# MD017A_ISO-F28027F_0.net
KiCad netlist of a schematic drawn in Altium Designer
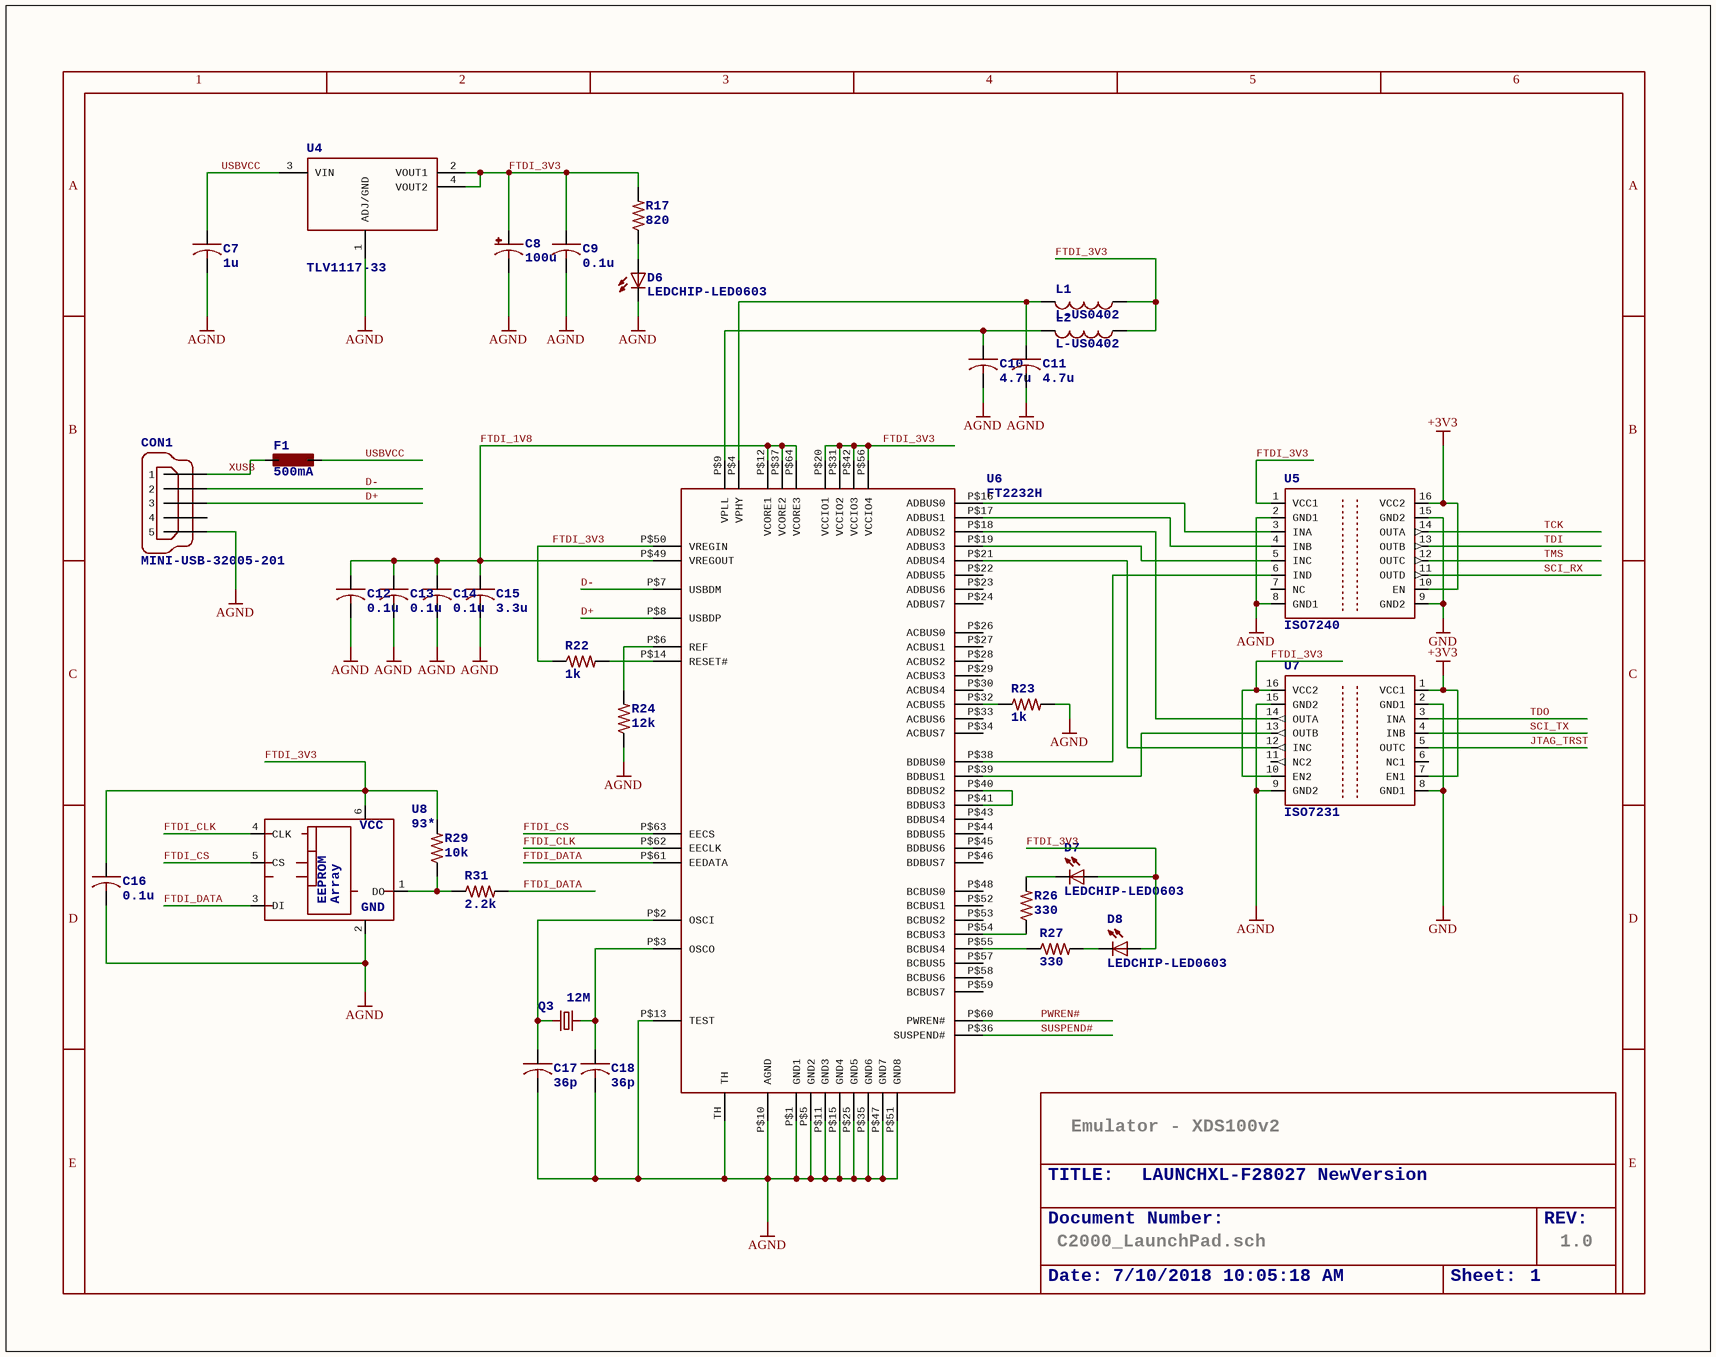
[diagram p0: MD017A ISO-F28027F_0.SchDoc]

(export (version "E")
  (design (tool "Eeschema 10.0.6"))
  (components
    (comp (ref "C7")
      (value "1u")
      (footprint "C0402")
      (description "CAPACITOR, American symbol")
      (libsource (lib "rcl") (part "C-USC0402"))
    )
    (comp (ref "C8")
      (value "100u")
      (footprint "B/3528-21R")
      (description "POLARIZED CAPACITOR, American symbol")
      (libsource (lib "rcl") (part "CPOL-USB/3528-21R"))
    )
    (comp (ref "C9")
      (value "0.1u")
      (footprint "C0402")
      (description "CAPACITOR, American symbol")
      (libsource (lib "rcl") (part "C-USC0402"))
    )
    (comp (ref "C10")
      (value "4.7u")
      (footprint "C0402")
      (description "CAPACITOR, American symbol")
      (libsource (lib "rcl") (part "C-USC0402"))
    )
    (comp (ref "C11")
      (value "4.7u")
      (footprint "C0402")
      (description "CAPACITOR, American symbol")
      (libsource (lib "rcl") (part "C-USC0402"))
    )
    (comp (ref "C12")
      (value "0.1u")
      (footprint "C0402")
      (description "CAPACITOR, American symbol")
      (libsource (lib "rcl") (part "C-USC0402"))
    )
    (comp (ref "C13")
      (value "0.1u")
      (footprint "C0402")
      (description "CAPACITOR, American symbol")
      (libsource (lib "rcl") (part "C-USC0402"))
    )
    (comp (ref "C14")
      (value "0.1u")
      (footprint "C0402")
      (description "CAPACITOR, American symbol")
      (libsource (lib "rcl") (part "C-USC0402"))
    )
    (comp (ref "C15")
      (value "3.3u")
      (footprint "C0402")
      (description "CAPACITOR, American symbol")
      (libsource (lib "rcl") (part "C-USC0402"))
    )
    (comp (ref "C16")
      (value "0.1u")
      (footprint "C0402")
      (description "CAPACITOR, American symbol")
      (libsource (lib "rcl") (part "C-USC0402"))
    )
    (comp (ref "C17")
      (value "36p")
      (footprint "C0402")
      (description "CAPACITOR, American symbol")
      (libsource (lib "rcl") (part "C-USC0402"))
    )
    (comp (ref "C18")
      (value "36p")
      (footprint "C0402")
      (description "CAPACITOR, American symbol")
      (libsource (lib "rcl") (part "C-USC0402"))
    )
    (comp (ref "CON1")
      (value "MINI-USB-32005-201")
      (footprint "32005-201")
      (description "MINI USB-B Conector   Source: www.cypressindustries.com")
      (libsource (lib "con-cypressindustries") (part "MINI-USB-32005-201"))
    )
    (comp (ref "D6")
      (value "LEDCHIP-LED0603")
      (footprint "CHIP-LED0603")
      (libsource (lib "led") (part "LEDCHIP-LED0603"))
    )
    (comp (ref "D7")
      (value "LEDCHIP-LED0603")
      (footprint "CHIP-LED0603")
      (libsource (lib "led") (part "LEDCHIP-LED0603"))
    )
    (comp (ref "D8")
      (value "LEDCHIP-LED0603")
      (footprint "CHIP-LED0603")
      (libsource (lib "led") (part "LEDCHIP-LED0603"))
    )
    (comp (ref "F1")
      (value "500mA")
      (footprint "L1812")
      (description "INDUCTOR, European symbol")
      (libsource (lib "rcl") (part "L-EUL1812"))
    )
    (comp (ref "L1")
      (value "L-US0402")
      (footprint "R0402")
      (description "INDUCTOR, American symbol")
      (libsource (lib "rcl") (part "L-US0402"))
    )
    (comp (ref "L2")
      (value "L-US0402")
      (footprint "R0402")
      (description "INDUCTOR, American symbol")
      (libsource (lib "rcl") (part "L-US0402"))
    )
    (comp (ref "Q3")
      (value "12M")
      (footprint "HC49UP")
      (description "CRYSTAL")
      (libsource (lib "crystal") (part "CRYSTALHC49UP"))
    )
    (comp (ref "R17")
      (value "820")
      (footprint "R0402")
      (description "RESISTOR, American symbol")
      (libsource (lib "rcl") (part "R-US_R0402"))
    )
    (comp (ref "R22")
      (value "1k")
      (footprint "R0402")
      (description "RESISTOR, American symbol")
      (libsource (lib "rcl") (part "R-US_R0402"))
    )
    (comp (ref "R23")
      (value "1k")
      (footprint "R0402")
      (description "RESISTOR, American symbol")
      (libsource (lib "rcl") (part "R-US_R0402"))
    )
    (comp (ref "R24")
      (value "12k")
      (footprint "R0402")
      (description "RESISTOR, American symbol")
      (libsource (lib "rcl") (part "R-US_R0402"))
    )
    (comp (ref "R26")
      (value "330")
      (footprint "R0402")
      (description "RESISTOR, American symbol")
      (libsource (lib "rcl") (part "R-US_R0402"))
    )
    (comp (ref "R27")
      (value "330")
      (footprint "R0402")
      (description "RESISTOR, American symbol")
      (libsource (lib "rcl") (part "R-US_R0402"))
    )
    (comp (ref "R29")
      (value "10k")
      (footprint "R0402")
      (description "RESISTOR, American symbol")
      (libsource (lib "rcl") (part "R-US_R0402"))
    )
    (comp (ref "R31")
      (value "2.2k")
      (footprint "R0402")
      (description "RESISTOR, American symbol")
      (libsource (lib "rcl") (part "R-US_R0402"))
    )
    (comp (ref "U4") (value "TLV1117-33") (footprint "SOT223") (libsource (lib "texas") (part "TLV1117-33")))
    (comp (ref "U5")
      (value "ISO7240")
      (footprint "SO-16DW")
      (description "HIGH SPEED QUAD DIGITAL ISOLATORS   Source: http://focus.ti.com/lit/ds/symlink/iso7240m.pdf")
      (fields (field (name "MPN") "ISO7240MDW"))
      (libsource (lib "texas") (part "ISO7240"))
    )
    (comp (ref "U6") (value "FT2232H") (footprint "QFN64") (libsource (lib "ti_trey") (part "FT2232H")))
    (comp (ref "U7") (value "ISO7231") (footprint "SO-16DW") (libsource (lib "texas") (part "ISO7231")))
    (comp (ref "U8")
      (value "93*")
      (footprint "SOT23-6")
      (description "Serial EPROM   1 K/2 K/4 K, low voltage, Microwire")
      (fields
        (field (name "ARRAY") "Array")
        (field (name "VCC") "VCC")
        (field (name "GND") "GND")
        (field (name "EEPROM") "EEPROM")
      )
      (libsource (lib "ti_trey") (part "93*"))
    )
  )
  (nets
    (net (code "1") (name "+3V3") (class "Default")
      (node (ref "U5") (pin "10") (pinfunction "EN_10") (pintype "passive"))
      (node (ref "U5") (pin "16") (pinfunction "VCC2_16") (pintype "power_in"))
      (node (ref "U7") (pin "1") (pinfunction "VCC1_1") (pintype "power_in"))
      (node (ref "U7") (pin "7") (pinfunction "EN1_7") (pintype "passive"))
    )
    (net (code "2") (name "/D+") (class "Default")
      (node (ref "CON1") (pin "3") (pinfunction "3_3") (pintype "passive"))
      (node (ref "U6") (pin "P$8") (pinfunction "USBDP_P$8") (pintype "passive"))
    )
    (net (code "3") (name "/D-") (class "Default")
      (node (ref "CON1") (pin "2") (pinfunction "2_2") (pintype "passive"))
      (node (ref "U6") (pin "P$7") (pinfunction "USBDM_P$7") (pintype "passive"))
    )
    (net (code "4") (name "/FTDI_1V8") (class "Default")
      (node (ref "C12") (pin "1") (pinfunction "1_1") (pintype "passive"))
      (node (ref "C13") (pin "1") (pinfunction "1_1") (pintype "passive"))
      (node (ref "C14") (pin "1") (pinfunction "1_1") (pintype "passive"))
      (node (ref "C15") (pin "1") (pinfunction "1_1") (pintype "passive"))
      (node (ref "U6") (pin "P$12") (pinfunction "VCORE1_P$12") (pintype "passive"))
      (node (ref "U6") (pin "P$37") (pinfunction "VCORE2_P$37") (pintype "passive"))
      (node (ref "U6") (pin "P$49") (pinfunction "VREGOUT_P$49") (pintype "passive"))
      (node (ref "U6") (pin "P$64") (pinfunction "VCORE3_P$64") (pintype "passive"))
    )
    (net (code "5") (name "/FTDI_3V3") (class "Default")
      (node (ref "C16") (pin "1") (pinfunction "1_1") (pintype "passive"))
      (node (ref "C8") (pin "+") (pinfunction "+_+") (pintype "passive"))
      (node (ref "C9") (pin "1") (pinfunction "1_1") (pintype "passive"))
      (node (ref "D7") (pin "A") (pinfunction "A_A") (pintype "passive"))
      (node (ref "D8") (pin "A") (pinfunction "A_A") (pintype "passive"))
      (node (ref "L1") (pin "1") (pinfunction "1_1") (pintype "passive"))
      (node (ref "L2") (pin "1") (pinfunction "1_1") (pintype "passive"))
      (node (ref "R17") (pin "2") (pinfunction "2_2") (pintype "passive"))
      (node (ref "R22") (pin "1") (pinfunction "1_1") (pintype "passive"))
      (node (ref "R29") (pin "2") (pinfunction "2_2") (pintype "passive"))
      (node (ref "U4") (pin "2") (pinfunction "VOUT1_2") (pintype "passive"))
      (node (ref "U4") (pin "4") (pinfunction "VOUT2_4") (pintype "passive"))
      (node (ref "U5") (pin "1") (pinfunction "VCC1_1") (pintype "power_in"))
      (node (ref "U6") (pin "P$20") (pinfunction "VCCIO1_P$20") (pintype "passive"))
      (node (ref "U6") (pin "P$31") (pinfunction "VCCIO2_P$31") (pintype "passive"))
      (node (ref "U6") (pin "P$42") (pinfunction "VCCIO3_P$42") (pintype "passive"))
      (node (ref "U6") (pin "P$50") (pinfunction "VREGIN_P$50") (pintype "passive"))
      (node (ref "U6") (pin "P$56") (pinfunction "VCCIO4_P$56") (pintype "passive"))
      (node (ref "U7") (pin "10") (pinfunction "EN2_10") (pintype "passive"))
      (node (ref "U7") (pin "16") (pinfunction "VCC2_16") (pintype "power_in"))
      (node (ref "U8") (pin "6") (pinfunction "VCC_6") (pintype "power_in"))
    )
    (net (code "6") (name "/FTDI_CLK") (class "Default")
      (node (ref "U6") (pin "P$62") (pinfunction "EECLK_P$62") (pintype "passive"))
      (node (ref "U8") (pin "4") (pinfunction "CLK_4") (pintype "passive"))
    )
    (net (code "7") (name "/FTDI_CS") (class "Default")
      (node (ref "U6") (pin "P$63") (pinfunction "EECS_P$63") (pintype "passive"))
      (node (ref "U8") (pin "5") (pinfunction "CS_5") (pintype "passive"))
    )
    (net (code "8") (name "/FTDI_DATA") (class "Default")
      (node (ref "R31") (pin "2") (pinfunction "2_2") (pintype "passive"))
      (node (ref "U6") (pin "P$61") (pinfunction "EEDATA_P$61") (pintype "passive"))
      (node (ref "U8") (pin "3") (pinfunction "DI_3") (pintype "passive"))
    )
    (net (code "9") (name "/JTAG_TRST") (class "Default")
      (node (ref "U7") (pin "5") (pinfunction "OUTC_5") (pintype "passive"))
    )
    (net (code "10") (name "/PWREN#") (class "Default")
      (node (ref "U6") (pin "P$60") (pinfunction "PWREN#_P$60") (pintype "passive"))
    )
    (net (code "11") (name "/SCI_RX") (class "Default")
      (node (ref "U5") (pin "11") (pinfunction "OUTD_11") (pintype "output"))
    )
    (net (code "12") (name "/SCI_TX") (class "Default")
      (node (ref "U7") (pin "4") (pinfunction "INB_4") (pintype "passive"))
    )
    (net (code "13") (name "/SUSPEND#") (class "Default")
      (node (ref "U6") (pin "P$36") (pinfunction "SUSPEND#_P$36") (pintype "passive"))
    )
    (net (code "14") (name "/TCK") (class "Default")
      (node (ref "U5") (pin "14") (pinfunction "OUTA_14") (pintype "output"))
    )
    (net (code "15") (name "/TDI") (class "Default")
      (node (ref "U5") (pin "13") (pinfunction "OUTB_13") (pintype "output"))
    )
    (net (code "16") (name "/TDO") (class "Default")
      (node (ref "U7") (pin "3") (pinfunction "INA_3") (pintype "passive"))
    )
    (net (code "17") (name "/TMS") (class "Default")
      (node (ref "U5") (pin "12") (pinfunction "OUTC_12") (pintype "output"))
    )
    (net (code "18") (name "/USBVCC") (class "Default")
      (node (ref "C7") (pin "1") (pinfunction "1_1") (pintype "passive"))
      (node (ref "F1") (pin "1") (pinfunction "1_1") (pintype "passive"))
      (node (ref "U4") (pin "3") (pinfunction "VIN_3") (pintype "passive"))
    )
    (net (code "19") (name "/XUSB") (class "Default")
      (node (ref "CON1") (pin "1") (pinfunction "1_1") (pintype "passive"))
      (node (ref "F1") (pin "2") (pinfunction "2_2") (pintype "passive"))
    )
    (net (code "20") (name "AGND") (class "Default")
      (node (ref "C10") (pin "2") (pinfunction "2_2") (pintype "passive"))
      (node (ref "C11") (pin "2") (pinfunction "2_2") (pintype "passive"))
      (node (ref "C12") (pin "2") (pinfunction "2_2") (pintype "passive"))
      (node (ref "C13") (pin "2") (pinfunction "2_2") (pintype "passive"))
      (node (ref "C14") (pin "2") (pinfunction "2_2") (pintype "passive"))
      (node (ref "C15") (pin "2") (pinfunction "2_2") (pintype "passive"))
      (node (ref "C16") (pin "2") (pinfunction "2_2") (pintype "passive"))
      (node (ref "C17") (pin "2") (pinfunction "2_2") (pintype "passive"))
      (node (ref "C18") (pin "2") (pinfunction "2_2") (pintype "passive"))
      (node (ref "C7") (pin "2") (pinfunction "2_2") (pintype "passive"))
      (node (ref "C8") (pin "-") (pinfunction "-_-") (pintype "passive"))
      (node (ref "C9") (pin "2") (pinfunction "2_2") (pintype "passive"))
      (node (ref "CON1") (pin "5") (pinfunction "5_5") (pintype "passive"))
      (node (ref "D6") (pin "C") (pinfunction "C_C") (pintype "passive"))
      (node (ref "R23") (pin "2") (pinfunction "2_2") (pintype "passive"))
      (node (ref "R24") (pin "1") (pinfunction "1_1") (pintype "passive"))
      (node (ref "U4") (pin "1") (pinfunction "ADJ/GND_1") (pintype "passive"))
      (node (ref "U5") (pin "2") (pinfunction "GND1_2") (pintype "power_in"))
      (node (ref "U5") (pin "8") (pinfunction "GND1_8") (pintype "power_in"))
      (node (ref "U6") (pin "P$1") (pinfunction "GND1_P$1") (pintype "passive"))
      (node (ref "U6") (pin "P$10") (pinfunction "AGND_P$10") (pintype "passive"))
      (node (ref "U6") (pin "P$11") (pinfunction "GND3_P$11") (pintype "passive"))
      (node (ref "U6") (pin "P$13") (pinfunction "TEST_P$13") (pintype "passive"))
      (node (ref "U6") (pin "P$15") (pinfunction "GND4_P$15") (pintype "passive"))
      (node (ref "U6") (pin "P$25") (pinfunction "GND5_P$25") (pintype "passive"))
      (node (ref "U6") (pin "P$35") (pinfunction "GND6_P$35") (pintype "passive"))
      (node (ref "U6") (pin "P$47") (pinfunction "GND7_P$47") (pintype "passive"))
      (node (ref "U6") (pin "P$5") (pinfunction "GND2_P$5") (pintype "passive"))
      (node (ref "U6") (pin "P$51") (pinfunction "GND8_P$51") (pintype "passive"))
      (node (ref "U6") (pin "TH") (pinfunction "TH_TH") (pintype "passive"))
      (node (ref "U7") (pin "15") (pinfunction "GND2_15") (pintype "power_in"))
      (node (ref "U7") (pin "9") (pinfunction "GND2_9") (pintype "power_in"))
      (node (ref "U8") (pin "2") (pinfunction "GND_2") (pintype "power_in"))
    )
    (net (code "21") (name "GND") (class "Default")
      (node (ref "U5") (pin "15") (pinfunction "GND2_15") (pintype "power_in"))
      (node (ref "U5") (pin "9") (pinfunction "GND2_9") (pintype "power_in"))
      (node (ref "U7") (pin "2") (pinfunction "GND1_2") (pintype "power_in"))
      (node (ref "U7") (pin "8") (pinfunction "GND1_8") (pintype "power_in"))
    )
    (net (code "22") (name "Net-(D6-PadA)") (class "Default")
      (node (ref "D6") (pin "A") (pinfunction "A_A") (pintype "passive"))
      (node (ref "R17") (pin "1") (pinfunction "1_1") (pintype "passive"))
    )
    (net (code "23") (name "Net-(D7-PadC)") (class "Default")
      (node (ref "D7") (pin "C") (pinfunction "C_C") (pintype "passive"))
      (node (ref "R26") (pin "2") (pinfunction "2_2") (pintype "passive"))
    )
    (net (code "24") (name "Net-(D8-PadC)") (class "Default")
      (node (ref "D8") (pin "C") (pinfunction "C_C") (pintype "passive"))
      (node (ref "R27") (pin "2") (pinfunction "2_2") (pintype "passive"))
    )
    (net (code "25") (name "Net-(U5-INA)") (class "Default")
      (node (ref "U5") (pin "3") (pinfunction "INA_3") (pintype "passive"))
      (node (ref "U6") (pin "P$16") (pinfunction "ADBUS0_P$16") (pintype "passive"))
    )
    (net (code "26") (name "Net-(U5-INB)") (class "Default")
      (node (ref "U5") (pin "4") (pinfunction "INB_4") (pintype "passive"))
      (node (ref "U6") (pin "P$17") (pinfunction "ADBUS1_P$17") (pintype "passive"))
    )
    (net (code "27") (name "Net-(U5-INC)") (class "Default")
      (node (ref "U5") (pin "5") (pinfunction "INC_5") (pintype "passive"))
      (node (ref "U6") (pin "P$19") (pinfunction "ADBUS3_P$19") (pintype "passive"))
    )
    (net (code "28") (name "Net-(U5-IND)") (class "Default")
      (node (ref "U5") (pin "6") (pinfunction "IND_6") (pintype "passive"))
      (node (ref "U6") (pin "P$38") (pinfunction "BDBUS0_P$38") (pintype "passive"))
    )
    (net (code "29") (name "Net-(U6-ACBUS5)") (class "Default")
      (node (ref "R23") (pin "1") (pinfunction "1_1") (pintype "passive"))
      (node (ref "U6") (pin "P$32") (pinfunction "ACBUS5_P$32") (pintype "passive"))
    )
    (net (code "30") (name "Net-(U6-ADBUS2)") (class "Default")
      (node (ref "U6") (pin "P$18") (pinfunction "ADBUS2_P$18") (pintype "passive"))
      (node (ref "U7") (pin "14") (pinfunction "OUTA_14") (pintype "output"))
    )
    (net (code "31") (name "Net-(U6-ADBUS4)") (class "Default")
      (node (ref "U6") (pin "P$21") (pinfunction "ADBUS4_P$21") (pintype "passive"))
      (node (ref "U7") (pin "12") (pinfunction "INC_12") (pintype "output"))
    )
    (net (code "32") (name "Net-(U6-BCBUS3)") (class "Default")
      (node (ref "R26") (pin "1") (pinfunction "1_1") (pintype "passive"))
      (node (ref "U6") (pin "P$54") (pinfunction "BCBUS3_P$54") (pintype "passive"))
    )
    (net (code "33") (name "Net-(U6-BCBUS4)") (class "Default")
      (node (ref "R27") (pin "1") (pinfunction "1_1") (pintype "passive"))
      (node (ref "U6") (pin "P$55") (pinfunction "BCBUS4_P$55") (pintype "passive"))
    )
    (net (code "34") (name "Net-(U6-BDBUS1)") (class "Default")
      (node (ref "U6") (pin "P$39") (pinfunction "BDBUS1_P$39") (pintype "passive"))
      (node (ref "U7") (pin "13") (pinfunction "OUTB_13") (pintype "output"))
    )
    (net (code "35") (name "Net-(U6-BDBUS2)") (class "Default")
      (node (ref "U6") (pin "P$40") (pinfunction "BDBUS2_P$40") (pintype "passive"))
      (node (ref "U6") (pin "P$41") (pinfunction "BDBUS3_P$41") (pintype "passive"))
    )
    (net (code "36") (name "Net-(U6-OSCI)") (class "Default")
      (node (ref "C17") (pin "1") (pinfunction "1_1") (pintype "passive"))
      (node (ref "Q3") (pin "1") (pinfunction "1_1") (pintype "passive"))
      (node (ref "U6") (pin "P$2") (pinfunction "OSCI_P$2") (pintype "passive"))
    )
    (net (code "37") (name "Net-(U6-OSCO)") (class "Default")
      (node (ref "C18") (pin "1") (pinfunction "1_1") (pintype "passive"))
      (node (ref "Q3") (pin "2") (pinfunction "2_2") (pintype "passive"))
      (node (ref "U6") (pin "P$3") (pinfunction "OSCO_P$3") (pintype "passive"))
    )
    (net (code "38") (name "Net-(U6-REF)") (class "Default")
      (node (ref "R24") (pin "2") (pinfunction "2_2") (pintype "passive"))
      (node (ref "U6") (pin "P$6") (pinfunction "REF_P$6") (pintype "passive"))
    )
    (net (code "39") (name "Net-(U6-RESET#)") (class "Default")
      (node (ref "R22") (pin "2") (pinfunction "2_2") (pintype "passive"))
      (node (ref "U6") (pin "P$14") (pinfunction "RESET#_P$14") (pintype "passive"))
    )
    (net (code "40") (name "Net-(U6-VPHY)") (class "Default")
      (node (ref "C11") (pin "1") (pinfunction "1_1") (pintype "passive"))
      (node (ref "L1") (pin "2") (pinfunction "2_2") (pintype "passive"))
      (node (ref "U6") (pin "P$4") (pinfunction "VPHY_P$4") (pintype "passive"))
    )
    (net (code "41") (name "Net-(U6-VPLL)") (class "Default")
      (node (ref "C10") (pin "1") (pinfunction "1_1") (pintype "passive"))
      (node (ref "L2") (pin "2") (pinfunction "2_2") (pintype "passive"))
      (node (ref "U6") (pin "P$9") (pinfunction "VPLL_P$9") (pintype "passive"))
    )
    (net (code "42") (name "Net-(U8-DO)") (class "Default")
      (node (ref "R29") (pin "1") (pinfunction "1_1") (pintype "passive"))
      (node (ref "R31") (pin "1") (pinfunction "1_1") (pintype "passive"))
      (node (ref "U8") (pin "1") (pinfunction "DO_1") (pintype "tri_state"))
    )
    (net (code "43") (name "unconnected-(CON1-Pad4)") (class "Default")
      (node (ref "CON1") (pin "4") (pinfunction "4_4") (pintype "passive"))
    )
    (net (code "44") (name "unconnected-(U5-NC-Pad7)") (class "Default")
      (node (ref "U5") (pin "7") (pinfunction "NC_7") (pintype "passive"))
    )
    (net (code "45") (name "unconnected-(U6-ACBUS0-PadP$26)") (class "Default")
      (node (ref "U6") (pin "P$26") (pinfunction "ACBUS0_P$26") (pintype "passive"))
    )
    (net (code "46") (name "unconnected-(U6-ACBUS1-PadP$27)") (class "Default")
      (node (ref "U6") (pin "P$27") (pinfunction "ACBUS1_P$27") (pintype "passive"))
    )
    (net (code "47") (name "unconnected-(U6-ACBUS2-PadP$28)") (class "Default")
      (node (ref "U6") (pin "P$28") (pinfunction "ACBUS2_P$28") (pintype "passive"))
    )
    (net (code "48") (name "unconnected-(U6-ACBUS3-PadP$29)") (class "Default")
      (node (ref "U6") (pin "P$29") (pinfunction "ACBUS3_P$29") (pintype "passive"))
    )
    (net (code "49") (name "unconnected-(U6-ACBUS4-PadP$30)") (class "Default")
      (node (ref "U6") (pin "P$30") (pinfunction "ACBUS4_P$30") (pintype "passive"))
    )
    (net (code "50") (name "unconnected-(U6-ACBUS6-PadP$33)") (class "Default")
      (node (ref "U6") (pin "P$33") (pinfunction "ACBUS6_P$33") (pintype "passive"))
    )
    (net (code "51") (name "unconnected-(U6-ACBUS7-PadP$34)") (class "Default")
      (node (ref "U6") (pin "P$34") (pinfunction "ACBUS7_P$34") (pintype "passive"))
    )
    (net (code "52") (name "unconnected-(U6-ADBUS5-PadP$22)") (class "Default")
      (node (ref "U6") (pin "P$22") (pinfunction "ADBUS5_P$22") (pintype "passive"))
    )
    (net (code "53") (name "unconnected-(U6-ADBUS6-PadP$23)") (class "Default")
      (node (ref "U6") (pin "P$23") (pinfunction "ADBUS6_P$23") (pintype "passive"))
    )
    (net (code "54") (name "unconnected-(U6-ADBUS7-PadP$24)") (class "Default")
      (node (ref "U6") (pin "P$24") (pinfunction "ADBUS7_P$24") (pintype "passive"))
    )
    (net (code "55") (name "unconnected-(U6-BCBUS0-PadP$48)") (class "Default")
      (node (ref "U6") (pin "P$48") (pinfunction "BCBUS0_P$48") (pintype "passive"))
    )
    (net (code "56") (name "unconnected-(U6-BCBUS1-PadP$52)") (class "Default")
      (node (ref "U6") (pin "P$52") (pinfunction "BCBUS1_P$52") (pintype "passive"))
    )
    (net (code "57") (name "unconnected-(U6-BCBUS2-PadP$53)") (class "Default")
      (node (ref "U6") (pin "P$53") (pinfunction "BCBUS2_P$53") (pintype "passive"))
    )
    (net (code "58") (name "unconnected-(U6-BCBUS5-PadP$57)") (class "Default")
      (node (ref "U6") (pin "P$57") (pinfunction "BCBUS5_P$57") (pintype "passive"))
    )
    (net (code "59") (name "unconnected-(U6-BCBUS6-PadP$58)") (class "Default")
      (node (ref "U6") (pin "P$58") (pinfunction "BCBUS6_P$58") (pintype "passive"))
    )
    (net (code "60") (name "unconnected-(U6-BCBUS7-PadP$59)") (class "Default")
      (node (ref "U6") (pin "P$59") (pinfunction "BCBUS7_P$59") (pintype "passive"))
    )
    (net (code "61") (name "unconnected-(U6-BDBUS4-PadP$43)") (class "Default")
      (node (ref "U6") (pin "P$43") (pinfunction "BDBUS4_P$43") (pintype "passive"))
    )
    (net (code "62") (name "unconnected-(U6-BDBUS5-PadP$44)") (class "Default")
      (node (ref "U6") (pin "P$44") (pinfunction "BDBUS5_P$44") (pintype "passive"))
    )
    (net (code "63") (name "unconnected-(U6-BDBUS6-PadP$45)") (class "Default")
      (node (ref "U6") (pin "P$45") (pinfunction "BDBUS6_P$45") (pintype "passive"))
    )
    (net (code "64") (name "unconnected-(U6-BDBUS7-PadP$46)") (class "Default")
      (node (ref "U6") (pin "P$46") (pinfunction "BDBUS7_P$46") (pintype "passive"))
    )
    (net (code "65") (name "unconnected-(U7-NC1-Pad6)") (class "Default")
      (node (ref "U7") (pin "6") (pinfunction "NC1_6") (pintype "passive"))
    )
    (net (code "66") (name "unconnected-(U7-NC2-Pad11)") (class "Default")
      (node (ref "U7") (pin "11") (pinfunction "NC2_11") (pintype "output"))
    )
  )
)
